# fpga-power-inside.net
KiCad netlist of a schematic drawn in Altium Designer
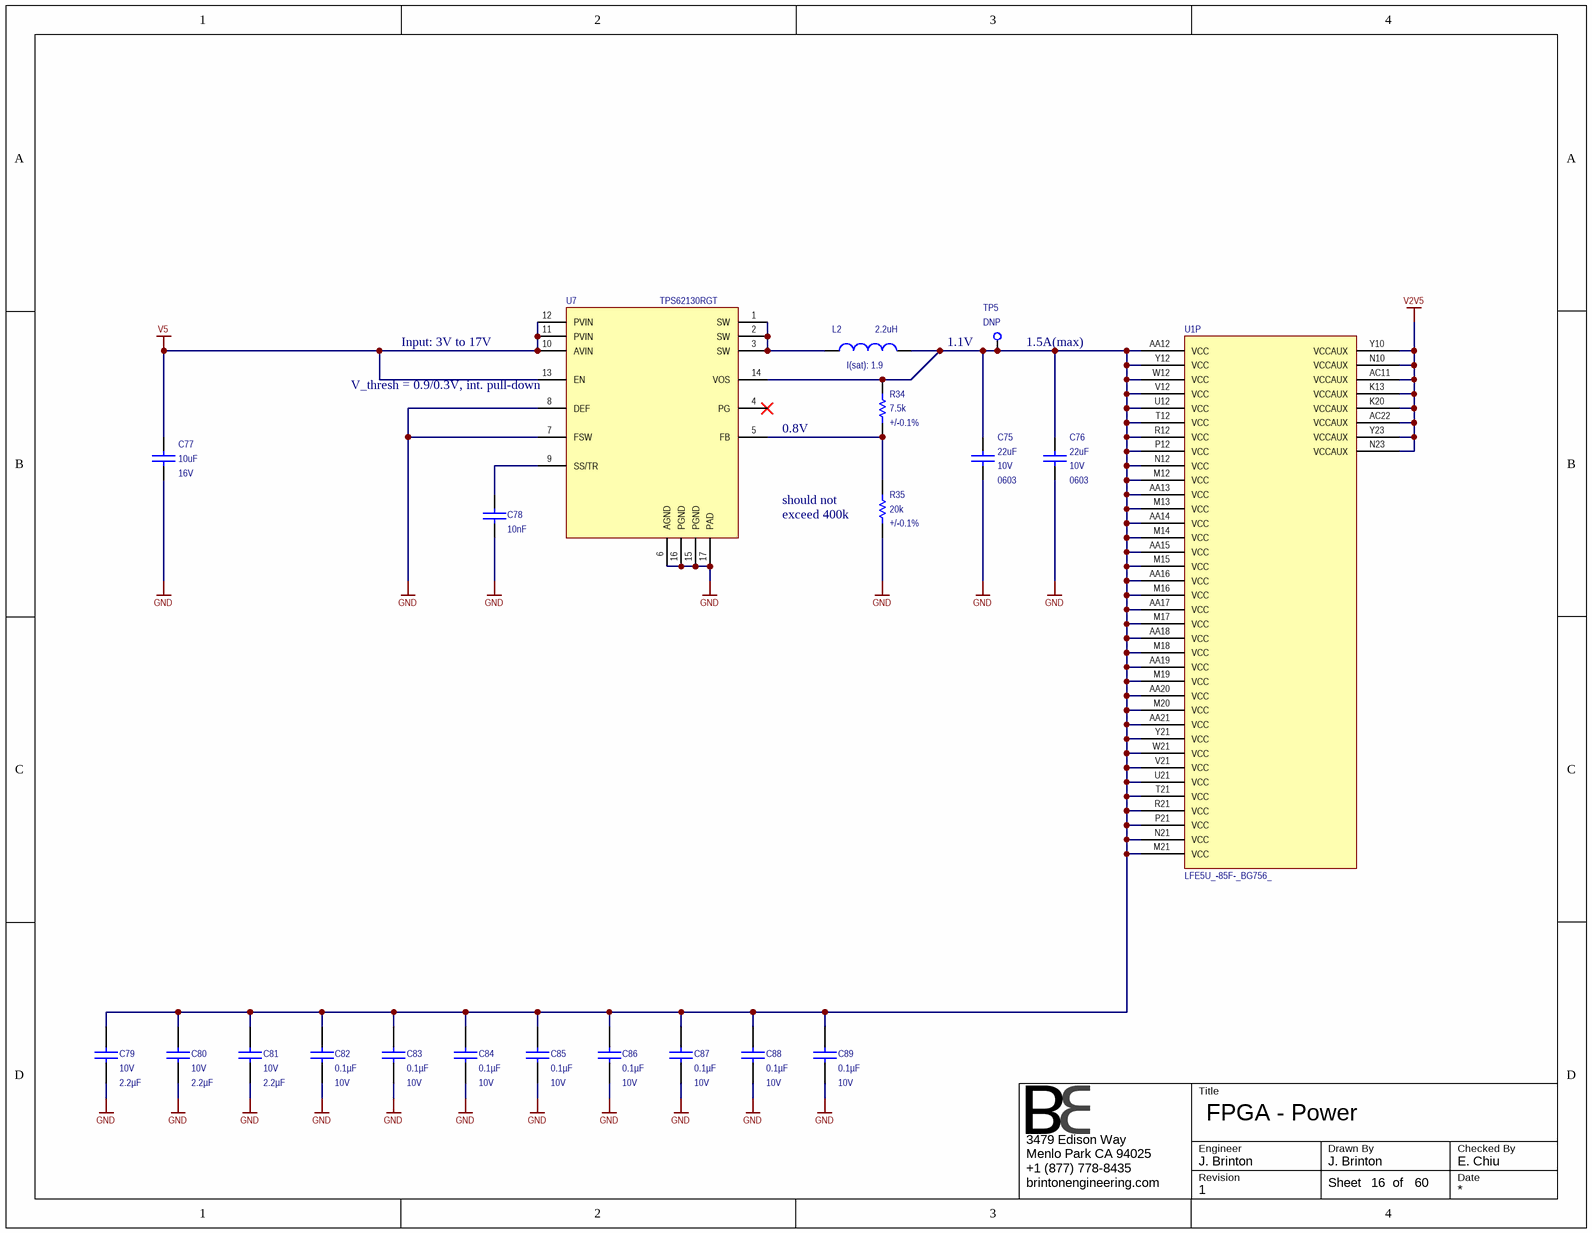
[diagram p0: fpga-power-inside.SchDoc]

(export (version "E")
  (design (tool "Eeschema 10.0.6"))
  (components
    (comp (ref "C75")
      (value "22uF")
      (footprint "0603")
      (description "Ceramic Capacitor 22uF +/-20% 10V X5R SMD 0603")
      (fields
        (field (name "MANUFACTURER") "TDK Corporation")
        (field (name "TOLERANCE") "+/-20%")
        (field (name "VOLTAGE") "10V")
      )
      (libsource (lib "") (part "CAP_1"))
    )
    (comp (ref "C76")
      (value "22uF")
      (footprint "0603")
      (description "Ceramic Capacitor 22uF +/-20% 10V X5R SMD 0603")
      (fields
        (field (name "MANUFACTURER") "TDK Corporation")
        (field (name "TOLERANCE") "+/-20%")
        (field (name "VOLTAGE") "10V")
      )
      (libsource (lib "") (part "CAP_1"))
    )
    (comp (ref "C77")
      (value "10uF")
      (footprint "0603")
      (description "Ceramic Capacitor 10uF +/-20% 16V X5R 0603")
      (fields
        (field (name "MANUFACTURER") "Taiyo Yuden")
        (field (name "VOLTAGE") "16V")
        (field (name "Comment") "CAP 10UF 0603")
      )
      (libsource (lib "generic") (part "CAP"))
    )
    (comp (ref "C78")
      (value "10nF")
      (footprint "0201")
      (description "Ceramic Capacitor 10nF +/-10% 10V X5R 0201")
      (fields (field (name "MANUFACTURER") "TDK Corporation") (field (name "VOLTAGE") "10V"))
      (libsource (lib "generic") (part "CAP"))
    )
    (comp (ref "C79")
      (value "GRM188R71A225KE15D")
      (footprint "CAPC1608X90N")
      (description "CAP CER 2.2UF 10V 10% X7R 0603")
      (fields
        (field (name "MANUFACTURER") "Murata Electronics North America")
        (field (name "TOLERANCE") "±10%")
        (field (name "VOLTAGE - RATED") "10V")
        (field (name "CAPACITANCE") "2.2µF")
      )
      (libsource (lib "murata") (part "GRM188R71A225KE15D"))
    )
    (comp (ref "C80")
      (value "GRM188R71A225KE15D")
      (footprint "CAPC1608X90N")
      (description "CAP CER 2.2UF 10V 10% X7R 0603")
      (fields
        (field (name "MANUFACTURER") "Murata Electronics North America")
        (field (name "TOLERANCE") "±10%")
        (field (name "VOLTAGE - RATED") "10V")
        (field (name "CAPACITANCE") "2.2µF")
      )
      (libsource (lib "murata") (part "GRM188R71A225KE15D"))
    )
    (comp (ref "C81")
      (value "GRM188R71A225KE15D")
      (footprint "CAPC1608X90N")
      (description "CAP CER 2.2UF 10V 10% X7R 0603")
      (fields
        (field (name "MANUFACTURER") "Murata Electronics North America")
        (field (name "TOLERANCE") "±10%")
        (field (name "VOLTAGE - RATED") "10V")
        (field (name "CAPACITANCE") "2.2µF")
      )
      (libsource (lib "murata") (part "GRM188R71A225KE15D"))
    )
    (comp (ref "C82")
      (value "GRM155R71A104KA01J")
      (footprint "CAPC1005X56N")
      (description "CAP CER 0.1UF 10V 10% X7R 0402")
      (fields
        (field (name "MANUFACTURER") "Murata Electronics North America")
        (field (name "TOLERANCE") "±10%")
        (field (name "CAPACITANCE") "0.1µF")
        (field (name "VOLTAGE - RATED") "10V")
      )
      (libsource (lib "murata") (part "GRM155R71A104KA01J"))
    )
    (comp (ref "C83")
      (value "GRM155R71A104KA01J")
      (footprint "CAPC1005X56N")
      (description "CAP CER 0.1UF 10V 10% X7R 0402")
      (fields
        (field (name "MANUFACTURER") "Murata Electronics North America")
        (field (name "TOLERANCE") "±10%")
        (field (name "CAPACITANCE") "0.1µF")
        (field (name "VOLTAGE - RATED") "10V")
      )
      (libsource (lib "murata") (part "GRM155R71A104KA01J"))
    )
    (comp (ref "C84")
      (value "GRM155R71A104KA01J")
      (footprint "CAPC1005X56N")
      (description "CAP CER 0.1UF 10V 10% X7R 0402")
      (fields
        (field (name "MANUFACTURER") "Murata Electronics North America")
        (field (name "TOLERANCE") "±10%")
        (field (name "CAPACITANCE") "0.1µF")
        (field (name "VOLTAGE - RATED") "10V")
      )
      (libsource (lib "murata") (part "GRM155R71A104KA01J"))
    )
    (comp (ref "C85")
      (value "GRM155R71A104KA01J")
      (footprint "CAPC1005X56N")
      (description "CAP CER 0.1UF 10V 10% X7R 0402")
      (fields
        (field (name "MANUFACTURER") "Murata Electronics North America")
        (field (name "TOLERANCE") "±10%")
        (field (name "CAPACITANCE") "0.1µF")
        (field (name "VOLTAGE - RATED") "10V")
      )
      (libsource (lib "murata") (part "GRM155R71A104KA01J"))
    )
    (comp (ref "C86")
      (value "GRM155R71A104KA01J")
      (footprint "CAPC1005X56N")
      (description "CAP CER 0.1UF 10V 10% X7R 0402")
      (fields
        (field (name "MANUFACTURER") "Murata Electronics North America")
        (field (name "TOLERANCE") "±10%")
        (field (name "CAPACITANCE") "0.1µF")
        (field (name "VOLTAGE - RATED") "10V")
      )
      (libsource (lib "murata") (part "GRM155R71A104KA01J"))
    )
    (comp (ref "C87")
      (value "GRM155R71A104KA01J")
      (footprint "CAPC1005X56N")
      (description "CAP CER 0.1UF 10V 10% X7R 0402")
      (fields
        (field (name "MANUFACTURER") "Murata Electronics North America")
        (field (name "TOLERANCE") "±10%")
        (field (name "CAPACITANCE") "0.1µF")
        (field (name "VOLTAGE - RATED") "10V")
      )
      (libsource (lib "murata") (part "GRM155R71A104KA01J"))
    )
    (comp (ref "C88")
      (value "GRM155R71A104KA01J")
      (footprint "CAPC1005X56N")
      (description "CAP CER 0.1UF 10V 10% X7R 0402")
      (fields
        (field (name "MANUFACTURER") "Murata Electronics North America")
        (field (name "TOLERANCE") "±10%")
        (field (name "CAPACITANCE") "0.1µF")
        (field (name "VOLTAGE - RATED") "10V")
      )
      (libsource (lib "murata") (part "GRM155R71A104KA01J"))
    )
    (comp (ref "C89")
      (value "GRM155R71A104KA01J")
      (footprint "CAPC1005X56N")
      (description "CAP CER 0.1UF 10V 10% X7R 0402")
      (fields
        (field (name "MANUFACTURER") "Murata Electronics North America")
        (field (name "TOLERANCE") "±10%")
        (field (name "CAPACITANCE") "0.1µF")
        (field (name "VOLTAGE - RATED") "10V")
      )
      (libsource (lib "murata") (part "GRM155R71A104KA01J"))
    )
    (comp (ref "L2")
      (value "2.2uH")
      (footprint "ASPI-3010FS")
      (description "Wirewound Inductor 2.2uH +/-20% 1.9A SMD 2518")
      (fields
        (field (name "MANUFACTURER") "Abracon")
        (field (name "I(SAT)") "1.9")
        (field (name "Comment") "ASPI-0310FS-2R2M-T2")
      )
      (libsource (lib "CamBoard_Pico_70.19K") (part "COIL"))
    )
    (comp (ref "R34")
      (value "7.5k")
      (footprint "RESC1608X55N")
      (description "Thick Film Resistor 7.5k Ohms +/-0.1% 0.1W 75V SMD 0603")
      (fields
        (field (name "TOLERANCE") "+/-0.1%")
        (field (name "MANUFACTURER") "Panasonic - ECG")
        (field (name "VOLTAGE") "75V")
      )
      (libsource (lib "brinton") (part "RES"))
    )
    (comp (ref "R35")
      (value "20k")
      (footprint "RESC1608X55N")
      (description "Thick Film Resistor 20k Ohms +/-0.1% 0.1W 75V SMD 0603")
      (fields
        (field (name "TOLERANCE") "+/-0.1%")
        (field (name "MANUFACTURER") "Panasonic - ECG")
        (field (name "VOLTAGE") "75V")
      )
      (libsource (lib "brinton") (part "RES"))
    )
    (comp (ref "TP5")
      (value "TEST_POINT")
      (footprint "TEST_POINT")
      (description "Thruhole Miniature Test Point")
      (fields (field (name "MANUFACTURER") "Keystone Electronics Corp") (field (name "DO NOT PLACE") "DNP"))
      (libsource (lib "generic") (part "TEST_POINT"))
    )
    (comp (ref "U1")
      (value "LFE5U_-85F-_BG756_")
      (footprint "lattice:caBGA756")
      (description "ECP5 FPGA, 85k LUT, 756-caBGA")
      (fields (field (name "MANUFACTURER") "Lattice Semiconductor"))
      (libsource (lib "lattice") (part "LFE5U_-85F-_BG756_"))
    )
    (comp (ref "U7")
      (value "TPS62130RGT")
      (footprint "S-PQFP-8N")
      (description "3-17V 3A Step-Down Converter VQFN")
      (fields (field (name "MANUFACTURER") "Texas Instruments"))
      (libsource (lib "ti") (part "TPS62130RGT"))
    )
  )
  (nets
    (net (code "1") (name "GND") (class "Default")
      (node (ref "C75") (pin "1") (pinfunction "1_1") (pintype "passive"))
      (node (ref "C76") (pin "1") (pinfunction "1_1") (pintype "passive"))
      (node (ref "C77") (pin "1") (pinfunction "1_1") (pintype "passive"))
      (node (ref "C78") (pin "2") (pinfunction "2_2") (pintype "passive"))
      (node (ref "C79") (pin "1") (pinfunction "1_1") (pintype "passive"))
      (node (ref "C80") (pin "1") (pinfunction "1_1") (pintype "passive"))
      (node (ref "C81") (pin "1") (pinfunction "1_1") (pintype "passive"))
      (node (ref "C82") (pin "1") (pinfunction "1_1") (pintype "passive"))
      (node (ref "C83") (pin "1") (pinfunction "1_1") (pintype "passive"))
      (node (ref "C84") (pin "1") (pinfunction "1_1") (pintype "passive"))
      (node (ref "C85") (pin "1") (pinfunction "1_1") (pintype "passive"))
      (node (ref "C86") (pin "1") (pinfunction "1_1") (pintype "passive"))
      (node (ref "C87") (pin "1") (pinfunction "1_1") (pintype "passive"))
      (node (ref "C88") (pin "1") (pinfunction "1_1") (pintype "passive"))
      (node (ref "C89") (pin "1") (pinfunction "1_1") (pintype "passive"))
      (node (ref "R35") (pin "1") (pinfunction "1_1") (pintype "passive"))
      (node (ref "U7") (pin "15") (pinfunction "PGND_15") (pintype "passive"))
      (node (ref "U7") (pin "16") (pinfunction "PGND_16") (pintype "passive"))
      (node (ref "U7") (pin "17") (pinfunction "PAD_17") (pintype "passive"))
      (node (ref "U7") (pin "6") (pinfunction "AGND_6") (pintype "passive"))
      (node (ref "U7") (pin "7") (pinfunction "FSW_7") (pintype "passive"))
      (node (ref "U7") (pin "8") (pinfunction "DEF_8") (pintype "passive"))
    )
    (net (code "2") (name "Net-(L2-Pad1)") (class "Default")
      (node (ref "L2") (pin "1") (pinfunction "1_1") (pintype "passive"))
      (node (ref "U7") (pin "1") (pinfunction "SW_1") (pintype "passive"))
      (node (ref "U7") (pin "2") (pinfunction "SW_2") (pintype "passive"))
      (node (ref "U7") (pin "3") (pinfunction "SW_3") (pintype "passive"))
    )
    (net (code "3") (name "Net-(U7-FB)") (class "Default")
      (node (ref "R34") (pin "1") (pinfunction "1_1") (pintype "passive"))
      (node (ref "R35") (pin "2") (pinfunction "2_2") (pintype "passive"))
      (node (ref "U7") (pin "5") (pinfunction "FB_5") (pintype "passive"))
    )
    (net (code "4") (name "Net-(U7-SS{slash}TR)") (class "Default")
      (node (ref "C78") (pin "1") (pinfunction "1_1") (pintype "passive"))
      (node (ref "U7") (pin "9") (pinfunction "SS/TR_9") (pintype "passive"))
    )
    (net (code "5") (name "Net-(U7-VOS)") (class "Default")
      (node (ref "C75") (pin "2") (pinfunction "2_2") (pintype "passive"))
      (node (ref "C76") (pin "2") (pinfunction "2_2") (pintype "passive"))
      (node (ref "C79") (pin "2") (pinfunction "2_2") (pintype "passive"))
      (node (ref "C80") (pin "2") (pinfunction "2_2") (pintype "passive"))
      (node (ref "C81") (pin "2") (pinfunction "2_2") (pintype "passive"))
      (node (ref "C82") (pin "2") (pinfunction "2_2") (pintype "passive"))
      (node (ref "C83") (pin "2") (pinfunction "2_2") (pintype "passive"))
      (node (ref "C84") (pin "2") (pinfunction "2_2") (pintype "passive"))
      (node (ref "C85") (pin "2") (pinfunction "2_2") (pintype "passive"))
      (node (ref "C86") (pin "2") (pinfunction "2_2") (pintype "passive"))
      (node (ref "C87") (pin "2") (pinfunction "2_2") (pintype "passive"))
      (node (ref "C88") (pin "2") (pinfunction "2_2") (pintype "passive"))
      (node (ref "C89") (pin "2") (pinfunction "2_2") (pintype "passive"))
      (node (ref "L2") (pin "2") (pinfunction "2_2") (pintype "passive"))
      (node (ref "R34") (pin "2") (pinfunction "2_2") (pintype "passive"))
      (node (ref "TP5") (pin "1") (pinfunction "1_1") (pintype "passive"))
      (node (ref "U1") (pin "AA12") (pinfunction "VCC_AA12") (pintype "power_in"))
      (node (ref "U1") (pin "AA13") (pinfunction "VCC_AA13") (pintype "power_in"))
      (node (ref "U1") (pin "AA14") (pinfunction "VCC_AA14") (pintype "power_in"))
      (node (ref "U1") (pin "AA15") (pinfunction "VCC_AA15") (pintype "power_in"))
      (node (ref "U1") (pin "AA16") (pinfunction "VCC_AA16") (pintype "power_in"))
      (node (ref "U1") (pin "AA17") (pinfunction "VCC_AA17") (pintype "power_in"))
      (node (ref "U1") (pin "AA18") (pinfunction "VCC_AA18") (pintype "power_in"))
      (node (ref "U1") (pin "AA19") (pinfunction "VCC_AA19") (pintype "power_in"))
      (node (ref "U1") (pin "AA20") (pinfunction "VCC_AA20") (pintype "power_in"))
      (node (ref "U1") (pin "AA21") (pinfunction "VCC_AA21") (pintype "power_in"))
      (node (ref "U1") (pin "M12") (pinfunction "VCC_M12") (pintype "power_in"))
      (node (ref "U1") (pin "M13") (pinfunction "VCC_M13") (pintype "power_in"))
      (node (ref "U1") (pin "M14") (pinfunction "VCC_M14") (pintype "power_in"))
      (node (ref "U1") (pin "M15") (pinfunction "VCC_M15") (pintype "power_in"))
      (node (ref "U1") (pin "M16") (pinfunction "VCC_M16") (pintype "power_in"))
      (node (ref "U1") (pin "M17") (pinfunction "VCC_M17") (pintype "power_in"))
      (node (ref "U1") (pin "M18") (pinfunction "VCC_M18") (pintype "power_in"))
      (node (ref "U1") (pin "M19") (pinfunction "VCC_M19") (pintype "power_in"))
      (node (ref "U1") (pin "M20") (pinfunction "VCC_M20") (pintype "power_in"))
      (node (ref "U1") (pin "M21") (pinfunction "VCC_M21") (pintype "power_in"))
      (node (ref "U1") (pin "N12") (pinfunction "VCC_N12") (pintype "power_in"))
      (node (ref "U1") (pin "N21") (pinfunction "VCC_N21") (pintype "power_in"))
      (node (ref "U1") (pin "P12") (pinfunction "VCC_P12") (pintype "power_in"))
      (node (ref "U1") (pin "P21") (pinfunction "VCC_P21") (pintype "power_in"))
      (node (ref "U1") (pin "R12") (pinfunction "VCC_R12") (pintype "power_in"))
      (node (ref "U1") (pin "R21") (pinfunction "VCC_R21") (pintype "power_in"))
      (node (ref "U1") (pin "T12") (pinfunction "VCC_T12") (pintype "power_in"))
      (node (ref "U1") (pin "T21") (pinfunction "VCC_T21") (pintype "power_in"))
      (node (ref "U1") (pin "U12") (pinfunction "VCC_U12") (pintype "power_in"))
      (node (ref "U1") (pin "U21") (pinfunction "VCC_U21") (pintype "power_in"))
      (node (ref "U1") (pin "V12") (pinfunction "VCC_V12") (pintype "power_in"))
      (node (ref "U1") (pin "V21") (pinfunction "VCC_V21") (pintype "power_in"))
      (node (ref "U1") (pin "W12") (pinfunction "VCC_W12") (pintype "power_in"))
      (node (ref "U1") (pin "W21") (pinfunction "VCC_W21") (pintype "power_in"))
      (node (ref "U1") (pin "Y12") (pinfunction "VCC_Y12") (pintype "power_in"))
      (node (ref "U1") (pin "Y21") (pinfunction "VCC_Y21") (pintype "power_in"))
      (node (ref "U7") (pin "14") (pinfunction "VOS_14") (pintype "passive"))
    )
    (net (code "6") (name "V2V5") (class "Default")
      (node (ref "U1") (pin "AC11") (pinfunction "VCCAUX_AC11") (pintype "power_in"))
      (node (ref "U1") (pin "AC22") (pinfunction "VCCAUX_AC22") (pintype "power_in"))
      (node (ref "U1") (pin "K13") (pinfunction "VCCAUX_K13") (pintype "power_in"))
      (node (ref "U1") (pin "K20") (pinfunction "VCCAUX_K20") (pintype "power_in"))
      (node (ref "U1") (pin "N10") (pinfunction "VCCAUX_N10") (pintype "power_in"))
      (node (ref "U1") (pin "N23") (pinfunction "VCCAUX_N23") (pintype "power_in"))
      (node (ref "U1") (pin "Y10") (pinfunction "VCCAUX_Y10") (pintype "power_in"))
      (node (ref "U1") (pin "Y23") (pinfunction "VCCAUX_Y23") (pintype "power_in"))
    )
    (net (code "7") (name "V5") (class "Default")
      (node (ref "C77") (pin "2") (pinfunction "2_2") (pintype "passive"))
      (node (ref "U7") (pin "10") (pinfunction "AVIN_10") (pintype "passive"))
      (node (ref "U7") (pin "11") (pinfunction "PVIN_11") (pintype "passive"))
      (node (ref "U7") (pin "12") (pinfunction "PVIN_12") (pintype "passive"))
      (node (ref "U7") (pin "13") (pinfunction "EN_13") (pintype "passive"))
    )
    (net (code "8") (name "unconnected-(U7-PG-Pad4)") (class "Default")
      (node (ref "U7") (pin "4") (pinfunction "PG_4") (pintype "passive+no_connect"))
    )
  )
)
